# fonte.net
KiCad netlist of a schematic drawn in EAGLE
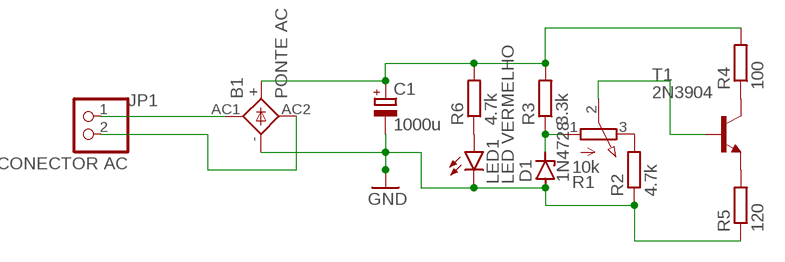
[diagram p0: schematic, sheet 1]

(export (version "E")
  (design (tool "Eeschema 10.0.6"))
  (components
    (comp (ref "B1")
      (value "PONTE AC")
      (footprint "eagle-import:1KAB")
      (libsource (lib "eagle-import") (part "1KAB"))
    )
    (comp (ref "C1")
      (value "1000u")
      (footprint "eagle-import:E5-10,5")
      (libsource (lib "eagle-import") (part "CPOL-EUE5-10.5"))
    )
    (comp (ref "D1")
      (value "1N4728")
      (footprint "eagle-import:DO41Z10")
      (libsource (lib "eagle-import") (part "1N4728"))
    )
    (comp (ref "JP1")
      (value "CONECTOR AC")
      (footprint "eagle-import:1X02")
      (libsource (lib "eagle-import") (part "PINHD-1X2"))
    )
    (comp (ref "LED1")
      (value "LED VERMELHO")
      (footprint "eagle-import:LED5MM")
      (libsource (lib "eagle-import") (part "LED5MM"))
    )
    (comp (ref "R1")
      (value "10k")
      (footprint "eagle-import:3RP_1610N")
      (libsource (lib "eagle-import") (part "3RP/1610N"))
    )
    (comp (ref "R2")
      (value "4.7k")
      (footprint "eagle-import:0207_10")
      (libsource (lib "eagle-import") (part "R-EU_0207/10"))
    )
    (comp (ref "R3")
      (value "3.3k")
      (footprint "eagle-import:0207_10")
      (libsource (lib "eagle-import") (part "R-EU_0207/10"))
    )
    (comp (ref "R4")
      (value "100")
      (footprint "eagle-import:0207_10")
      (libsource (lib "eagle-import") (part "R-EU_0207/10"))
    )
    (comp (ref "R5")
      (value "120")
      (footprint "eagle-import:0207_10")
      (libsource (lib "eagle-import") (part "R-EU_0207/10"))
    )
    (comp (ref "R6")
      (value "4.7k")
      (footprint "eagle-import:0207_10")
      (libsource (lib "eagle-import") (part "R-EU_0207/10"))
    )
    (comp (ref "T1")
      (value "2N3904")
      (footprint "eagle-import:TO92")
      (libsource (lib "eagle-import") (part "2N3904"))
    )
  )
  (nets
    (net (code "1") (name "GND") (class "Default")
      (node (ref "B1") (pin "-") (pinfunction "-_-") (pintype "passive"))
      (node (ref "C1") (pin "-") (pinfunction "-_-") (pintype "passive"))
      (node (ref "D1") (pin "A") (pinfunction "A_A") (pintype "passive"))
      (node (ref "LED1") (pin "K") (pinfunction "C_K") (pintype "passive"))
      (node (ref "R2") (pin "1") (pinfunction "1_1") (pintype "passive"))
      (node (ref "R5") (pin "1") (pinfunction "1_1") (pintype "passive"))
    )
    (net (code "2") (name "Net-(B1-Pad+)") (class "Default")
      (node (ref "B1") (pin "+") (pinfunction "+_+") (pintype "passive"))
      (node (ref "C1") (pin "+") (pinfunction "+_+") (pintype "passive"))
      (node (ref "R3") (pin "2") (pinfunction "2_2") (pintype "passive"))
      (node (ref "R4") (pin "2") (pinfunction "2_2") (pintype "passive"))
      (node (ref "R6") (pin "2") (pinfunction "2_2") (pintype "passive"))
    )
    (net (code "3") (name "Net-(B1-PadAC1)") (class "Default")
      (node (ref "B1") (pin "AC1") (pinfunction "AC1_AC1") (pintype "passive"))
      (node (ref "JP1") (pin "1") (pinfunction "1_1") (pintype "passive"))
    )
    (net (code "4") (name "Net-(B1-PadAC2)") (class "Default")
      (node (ref "B1") (pin "AC2") (pinfunction "AC2_AC2") (pintype "passive"))
      (node (ref "JP1") (pin "2") (pinfunction "2_2") (pintype "passive"))
    )
    (net (code "5") (name "Net-(LED1-PadA)") (class "Default")
      (node (ref "LED1") (pin "A") (pinfunction "A_A") (pintype "passive"))
      (node (ref "R6") (pin "1") (pinfunction "1_1") (pintype "passive"))
    )
    (net (code "6") (name "Net-(R1-A)") (class "Default")
      (node (ref "D1") (pin "C") (pinfunction "C_C") (pintype "passive"))
      (node (ref "R1") (pin "1") (pinfunction "A_1") (pintype "passive"))
      (node (ref "R3") (pin "1") (pinfunction "1_1") (pintype "passive"))
    )
    (net (code "7") (name "Net-(R1-E)") (class "Default")
      (node (ref "R1") (pin "3") (pinfunction "E_3") (pintype "passive"))
      (node (ref "R2") (pin "2") (pinfunction "2_2") (pintype "passive"))
    )
    (net (code "8") (name "Net-(R1-S)") (class "Default")
      (node (ref "R1") (pin "2") (pinfunction "S_2") (pintype "passive"))
      (node (ref "T1") (pin "2") (pinfunction "B_2") (pintype "passive"))
    )
    (net (code "9") (name "Net-(T1-C)") (class "Default")
      (node (ref "R4") (pin "1") (pinfunction "1_1") (pintype "passive"))
      (node (ref "T1") (pin "1") (pinfunction "C_1") (pintype "passive"))
    )
    (net (code "10") (name "Net-(T1-E)") (class "Default")
      (node (ref "R5") (pin "2") (pinfunction "2_2") (pintype "passive"))
      (node (ref "T1") (pin "3") (pinfunction "E_3") (pintype "passive"))
    )
  )
)
